# Sheet.net
KiCad netlist of a schematic drawn in Altium Designer
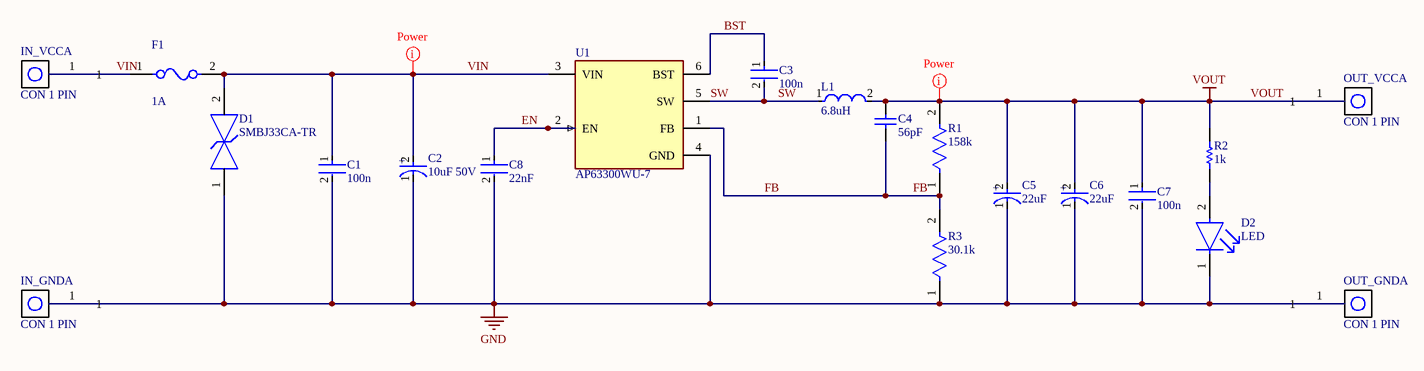
[diagram p0: Sheet.SchDoc]

(export (version "E")
  (design (tool "Eeschema 10.0.6"))
  (components
    (comp (ref "C1")
      (value "100n")
      (footprint "FP-0805-L_2_01_0_2-W_1_25-IPC_B")
      (description "Automotive Ceramic Capacitor, 0805, 100nF, 10%, X7R, 15%, 100V")
      (fields (field (name "TOLERANCE") "10%") (field (name "VOLTAGE") "100V"))
      (libsource (lib "Altium Content Vault") (part "b4654b650e69147ec39a6b967a45e02"))
    )
    (comp (ref "C2")
      (value "10uF 50V")
      (footprint "FP-FKD-MFG")
      (description "CAP ALUM 10UF 20% 50V SMD")
      (fields (field (name "VOLTAGE") "50V") (field (name "TOLERANCE") "20%"))
      (libsource (lib "Altium Content Vault") (part "203bc49f2ac43e59fd269a8c329ed05"))
    )
    (comp (ref "C3")
      (value "100n")
      (footprint "FP-0805-L_2_01_0_2-W_1_25-IPC_B")
      (description "Automotive Ceramic Capacitor, 0805, 100nF, 10%, X7R, 15%, 100V")
      (fields (field (name "TOLERANCE") "10%") (field (name "VOLTAGE") "100V"))
      (libsource (lib "Altium Content Vault") (part "b4654b650e69147ec39a6b967a45e02"))
    )
    (comp (ref "C4")
      (value "56pF")
      (footprint "CAPC2013X94X50ML20T25")
      (fields
        (field (name "MANUFACTURER") "AVX Interconnect / Elco")
        (field (name "PART NUMBER") "08055A560JAT2-A")
      )
      (libsource (lib "Altium Content Vault") (part "CAP"))
    )
    (comp (ref "C5")
      (value "22uF")
      (footprint "FP-FKD-MFG")
      (description "CAP ALUM 22UF 20% 50V SMD")
      (fields (field (name "TOLERANCE") "20%") (field (name "VOLTAGE") "50V"))
      (libsource (lib "Altium Content Vault") (part "203bc49f2ac43e59fd269a8c329ed05"))
    )
    (comp (ref "C6")
      (value "22uF")
      (footprint "FP-FKD-MFG")
      (description "CAP ALUM 22UF 20% 50V SMD")
      (fields (field (name "TOLERANCE") "20%") (field (name "VOLTAGE") "50V"))
      (libsource (lib "Altium Content Vault") (part "203bc49f2ac43e59fd269a8c329ed05"))
    )
    (comp (ref "C7")
      (value "100n")
      (footprint "FP-0805-L_2_01_0_2-W_1_25-IPC_B")
      (description "Automotive Ceramic Capacitor, 0805, 100nF, 10%, X7R, 15%, 100V")
      (fields (field (name "TOLERANCE") "10%") (field (name "VOLTAGE") "100V"))
      (libsource (lib "Altium Content Vault") (part "b4654b650e69147ec39a6b967a45e02"))
    )
    (comp (ref "C8")
      (value "22nF")
      (footprint "FP-C0805C-DN-MFG")
      (description "CAP CER 0.022UF 50V X7R 0805")
      (fields
        (field (name "MANUFACTURER") "KEMET")
        (field (name "MANUFACTURER PART NUMBER") "C0805C223K5RACTU")
      )
      (libsource (lib "Altium Content Vault") (part "b4654b650e69147ec39a6b967a45e02"))
    )
    (comp (ref "D1")
      (value "SMBJ33CA-TR")
      (footprint "FP-SMB-CA-MFG")
      (description "TVS DIODE 33V 69.7V SMB")
      (fields
        (field (name "OCTOPART") "https://octopart.com/smbj33ca-tr-stmicroelectronics-347069")
        (field (name "MANUFACTURER") "STMicroelectronics")
      )
      (libsource (lib "Altium Content Vault") (part "11bd9d59d340f0612179daf16ad9b72"))
    )
    (comp (ref "D2")
      (value "LED")
      (footprint "FP-LTST-C190GKT-MFG")
      (description "LED GREEN CLEAR CHIP SMD")
      (fields (field (name "VOLTAGE") "2V"))
      (libsource (lib "Altium Content Vault") (part "8706943c75ba83719d021d2fdc84c58"))
    )
    (comp (ref "F1")
      (value "1A")
      (footprint "FP-0451-MFG")
      (description "FUSE BRD MNT 1A 125VAC/VDC 2SMD")
      (fields
        (field (name "OCTOPART") "https://octopart.com/0451001.mrl-littelfuse-566368")
        (field (name "MANUFACTURER") "Littelfuse Inc")
      )
      (libsource (lib "Altium Content Vault") (part "5bcf9b9f640e542cf0359d10258e979"))
    )
    (comp (ref "IN_GND")
      (value "CON 1 PIN")
      (footprint "PCBComponent_1")
      (libsource (lib "Connector_3mm") (part "Connector_3mm"))
    )
    (comp (ref "IN_VCC")
      (value "CON 1 PIN")
      (footprint "PCBComponent_1")
      (libsource (lib "Connector_3mm") (part "Connector_3mm"))
    )
    (comp (ref "L1")
      (value "6.8uH")
      (footprint "FP-IHLP-2525CZ-FP_2_413x3-MFG")
      (description "Commercial Inductors, Low DCR Series 6.8uH 5.5A 46.8mΩ 20%")
      (fields (field (name "TOLERANCE") "20%"))
      (libsource (lib "Altium Content Vault") (part "725321dda6339637d4d059423bc1c3c"))
    )
    (comp (ref "OUT_GND")
      (value "CON 1 PIN")
      (footprint "PCBComponent_1")
      (libsource (lib "Connector_3mm") (part "Connector_3mm"))
    )
    (comp (ref "OUT_VCC")
      (value "CON 1 PIN")
      (footprint "PCBComponent_1")
      (libsource (lib "Connector_3mm") (part "Connector_3mm"))
    )
    (comp (ref "R1")
      (value "158k")
      (footprint "FP-CRCW0402-e3-IPC_C")
      (description "RES Thick Film, 158kΩ, 1%, 0.063W, 100ppm/°C, 0402")
      (fields (field (name "TOLERANCE") "1%"))
      (libsource (lib "Altium Content Vault") (part "1029c3af85768c4190bb7ad29bc67b5"))
    )
    (comp (ref "R2")
      (value "1k")
      (footprint "RESC2013X70X40ML20T20")
      (description "Chip Resistor, 1 KOhm, +/- 1%, 0.125 W, -55 to 155 degC, 0805 (2012 Metric), RoHS, Tape and Reel")
      (fields (field (name "MANUFACTURER") "Panasonic"))
      (libsource (lib "Altium Content Vault") (part "RES-2"))
    )
    (comp (ref "R3")
      (value "30.1k")
      (footprint "FP-CRCW0402-e3-IPC_A")
      (description "RES Thick Film, 30.1kΩ, 1%, 0.063W, 100ppm/°C, 0402")
      (fields (field (name "TOLERANCE") "1%"))
      (libsource (lib "Altium Content Vault") (part "1029c3af85768c4190bb7ad29bc67b5"))
    )
    (comp (ref "U1")
      (value "AP63300WU-7")
      (footprint "FP-TSOT26-IPC_A")
      (description "DCDC CONV HV BUCK TSOT26")
      (libsource (lib "Altium Content Vault") (part "1f55634e5cdcb17378ea3938d0fe863"))
    )
  )
  (nets
    (net (code "1") (name "/BST") (class "Default")
      (node (ref "C3") (pin "1") (pinfunction "1_1") (pintype "passive"))
      (node (ref "U1") (pin "6") (pinfunction "BST_6") (pintype "passive"))
    )
    (net (code "2") (name "/EN") (class "Default")
      (node (ref "C8") (pin "1") (pinfunction "1_1") (pintype "passive"))
      (node (ref "U1") (pin "2") (pinfunction "EN_2") (pintype "input"))
    )
    (net (code "3") (name "/FB") (class "Default")
      (node (ref "C4") (pin "1") (pinfunction "1_1") (pintype "passive"))
      (node (ref "R1") (pin "1") (pinfunction "1_1") (pintype "passive"))
      (node (ref "R3") (pin "2") (pinfunction "2_2") (pintype "passive"))
      (node (ref "U1") (pin "1") (pinfunction "FB_1") (pintype "passive"))
    )
    (net (code "4") (name "/SW") (class "Default")
      (node (ref "C3") (pin "2") (pinfunction "2_2") (pintype "passive"))
      (node (ref "L1") (pin "1") (pinfunction "1_1") (pintype "passive"))
      (node (ref "U1") (pin "5") (pinfunction "SW_5") (pintype "passive"))
    )
    (net (code "5") (name "/VIN") (class "Default")
      (node (ref "C1") (pin "1") (pinfunction "1_1") (pintype "passive"))
      (node (ref "C2") (pin "2") (pinfunction "A_2") (pintype "passive"))
      (node (ref "D1") (pin "2") (pinfunction "2_2") (pintype "passive"))
      (node (ref "F1") (pin "1") (pinfunction "1_1") (pintype "passive"))
      (node (ref "F1") (pin "2") (pinfunction "2_2") (pintype "passive"))
      (node (ref "IN_VCC") (pin "1") (pinfunction "1_1") (pintype "passive"))
      (node (ref "U1") (pin "3") (pinfunction "VIN_3") (pintype "power_in"))
    )
    (net (code "6") (name "GND") (class "Default")
      (node (ref "C1") (pin "2") (pinfunction "2_2") (pintype "passive"))
      (node (ref "C2") (pin "1") (pinfunction "C_1") (pintype "passive"))
      (node (ref "C5") (pin "1") (pinfunction "C_1") (pintype "passive"))
      (node (ref "C6") (pin "1") (pinfunction "C_1") (pintype "passive"))
      (node (ref "C7") (pin "2") (pinfunction "2_2") (pintype "passive"))
      (node (ref "C8") (pin "2") (pinfunction "2_2") (pintype "passive"))
      (node (ref "D1") (pin "1") (pinfunction "1_1") (pintype "passive"))
      (node (ref "D2") (pin "1") (pinfunction "C_1") (pintype "passive"))
      (node (ref "IN_GND") (pin "1") (pinfunction "1_1") (pintype "passive"))
      (node (ref "OUT_GND") (pin "1") (pinfunction "1_1") (pintype "passive"))
      (node (ref "R3") (pin "1") (pinfunction "1_1") (pintype "passive"))
      (node (ref "U1") (pin "4") (pinfunction "GND_4") (pintype "power_in"))
    )
    (net (code "7") (name "Net-(D2-A)") (class "Default")
      (node (ref "D2") (pin "2") (pinfunction "A_2") (pintype "passive"))
      (node (ref "R2") (pin "1") (pinfunction "1_1") (pintype "passive"))
    )
    (net (code "8") (name "VOUT") (class "Default")
      (node (ref "C4") (pin "2") (pinfunction "2_2") (pintype "passive"))
      (node (ref "C5") (pin "2") (pinfunction "A_2") (pintype "passive"))
      (node (ref "C6") (pin "2") (pinfunction "A_2") (pintype "passive"))
      (node (ref "C7") (pin "1") (pinfunction "1_1") (pintype "passive"))
      (node (ref "L1") (pin "2") (pinfunction "2_2") (pintype "passive"))
      (node (ref "OUT_VCC") (pin "1") (pinfunction "1_1") (pintype "passive"))
      (node (ref "R1") (pin "2") (pinfunction "2_2") (pintype "passive"))
      (node (ref "R2") (pin "2") (pinfunction "2_2") (pintype "passive"))
    )
  )
)
